# DA.net
KiCad netlist of a schematic drawn in EAGLE
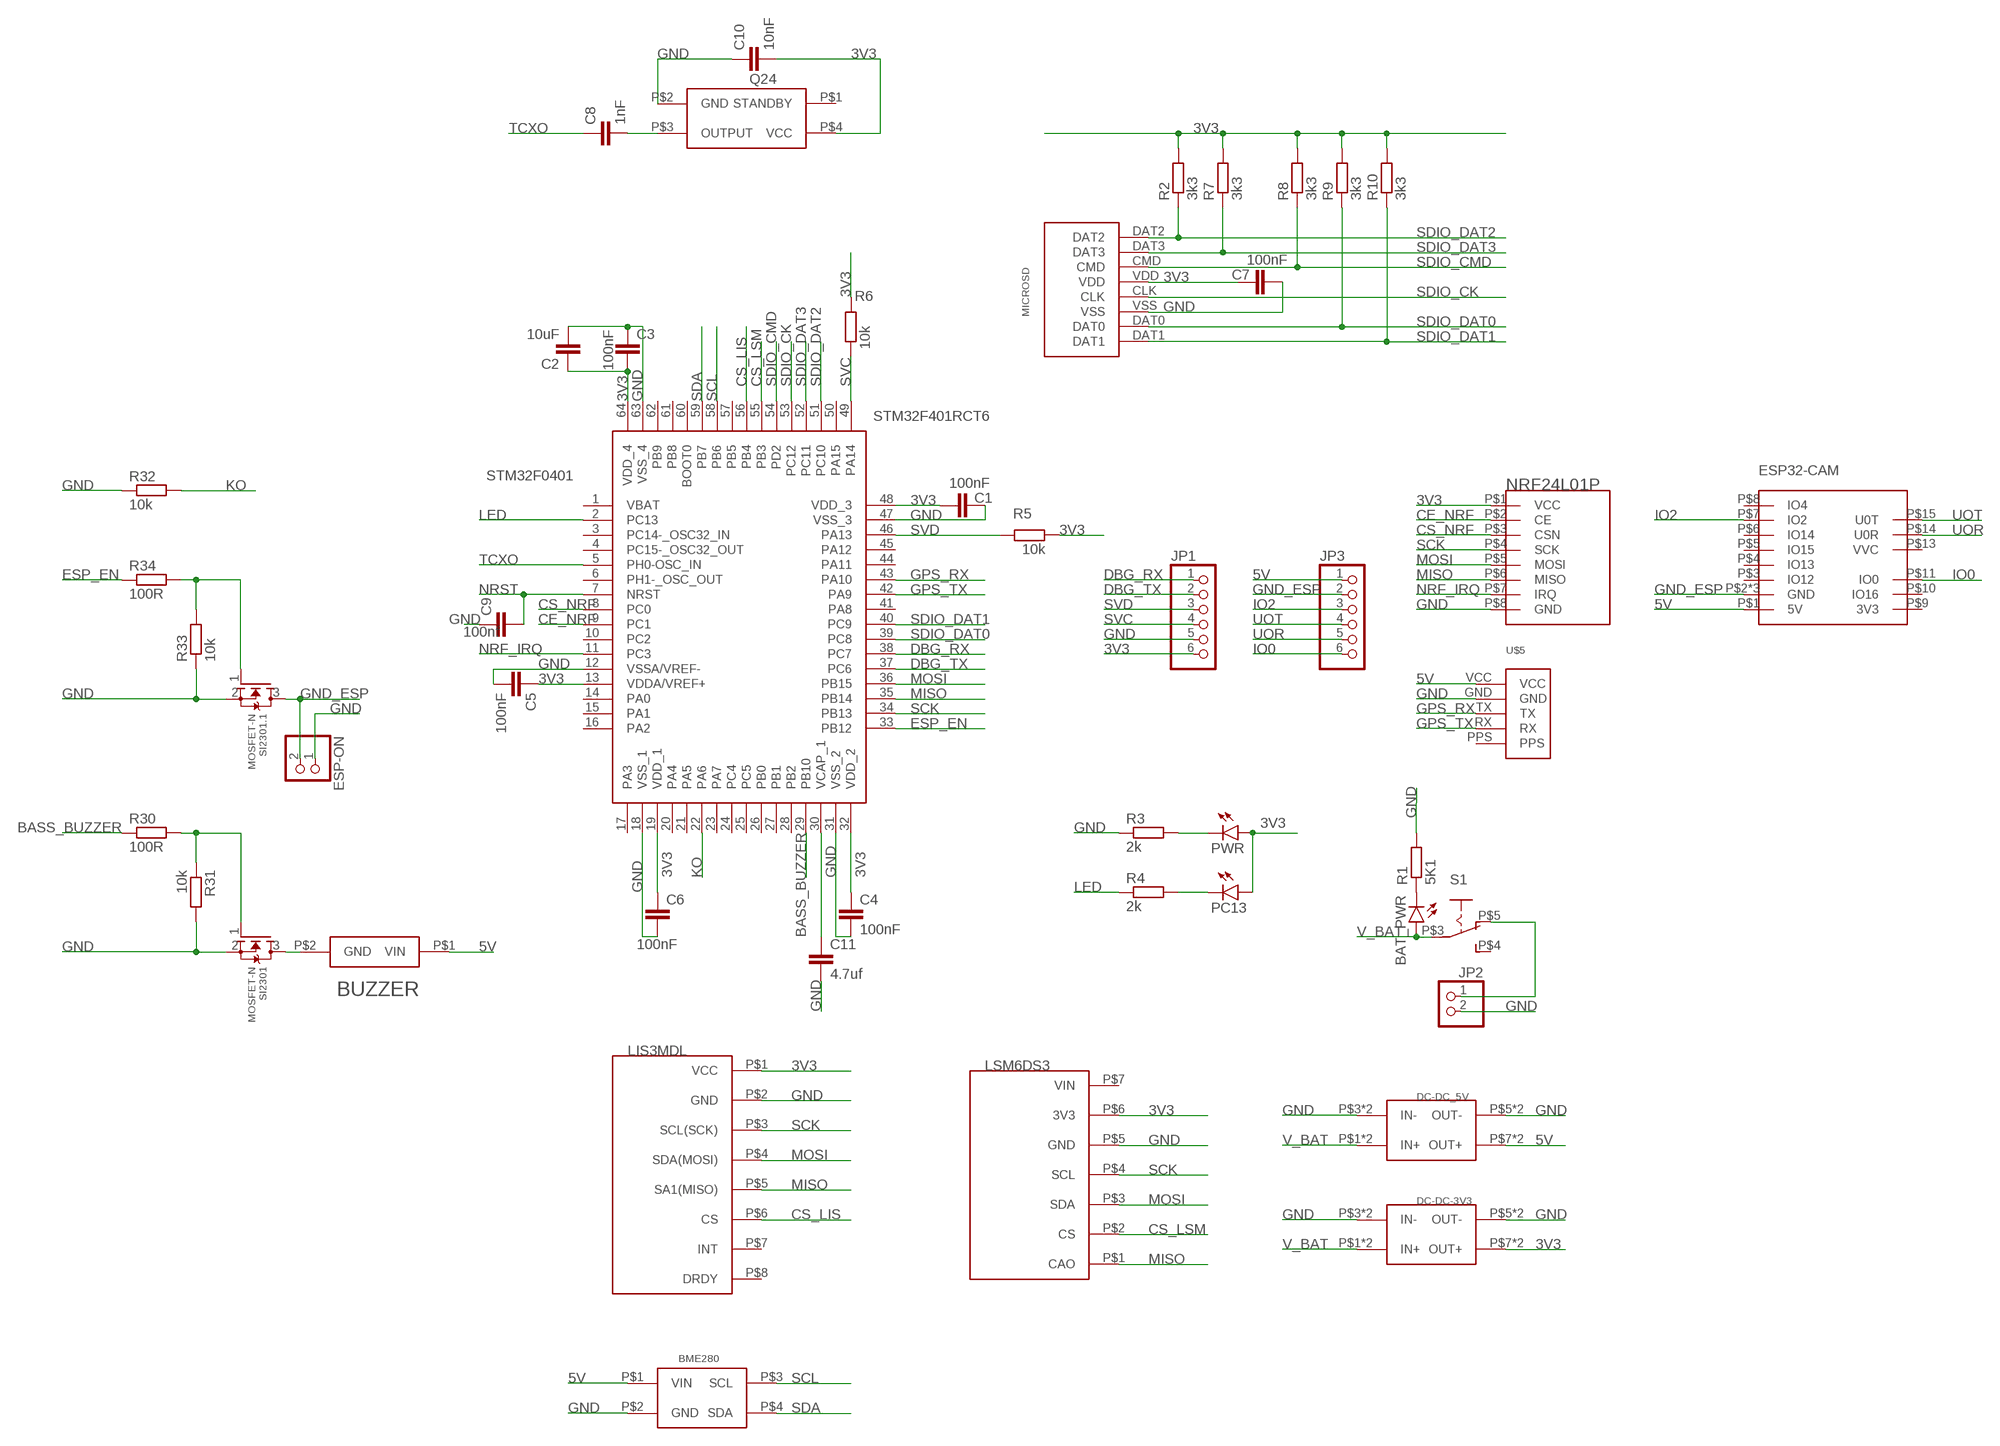
[diagram p0: schematic, sheet 1]

(export (version "E")
  (design (tool "Eeschema 10.0.6"))
  (components
    (comp (ref "BAT_PWR")
      (value "LEDSML0603")
      (footprint "eagle-import:SML0603")
      (libsource (lib "eagle-import") (part "LEDSML0603"))
    )
    (comp (ref "BME280")
      (value "BME280BME280-PINS-ONLY")
      (footprint "eagle-import:BME280-PINS-ONLY")
      (libsource (lib "eagle-import") (part "BME280BME280-PINS-ONLY"))
    )
    (comp (ref "BUZZER")
      (value "BUZZERS8R6")
      (footprint "eagle-import:BUZZER-S8R12")
      (libsource (lib "eagle-import") (part "BUZZERS8R6"))
    )
    (comp (ref "C1")
      (value "100nF")
      (footprint "eagle-import:C0603")
      (libsource (lib "eagle-import") (part "C-EUC0603"))
    )
    (comp (ref "C2")
      (value "10uF")
      (footprint "eagle-import:C1206")
      (libsource (lib "eagle-import") (part "C-EUC1206"))
    )
    (comp (ref "C3")
      (value "100nF")
      (footprint "eagle-import:C0603")
      (libsource (lib "eagle-import") (part "C-EUC0603"))
    )
    (comp (ref "C4")
      (value "100nF")
      (footprint "eagle-import:C0603")
      (libsource (lib "eagle-import") (part "C-EUC0603"))
    )
    (comp (ref "C5")
      (value "100nF")
      (footprint "eagle-import:C0603")
      (libsource (lib "eagle-import") (part "C-EUC0603"))
    )
    (comp (ref "C6")
      (value "100nF")
      (footprint "eagle-import:C0603")
      (libsource (lib "eagle-import") (part "C-EUC0603"))
    )
    (comp (ref "C7")
      (value "100nF")
      (footprint "eagle-import:C0603")
      (libsource (lib "eagle-import") (part "C-EUC0603"))
    )
    (comp (ref "C8")
      (value "1nF")
      (footprint "eagle-import:C0603")
      (libsource (lib "eagle-import") (part "C-EUC0603"))
    )
    (comp (ref "C9")
      (value "100nf")
      (footprint "eagle-import:C0603")
      (libsource (lib "eagle-import") (part "C-EUC0603"))
    )
    (comp (ref "C10")
      (value "10nF")
      (footprint "eagle-import:C0603")
      (libsource (lib "eagle-import") (part "C-EUC0603"))
    )
    (comp (ref "C11")
      (value "4.7uf")
      (footprint "eagle-import:C0603")
      (libsource (lib "eagle-import") (part "C-EUC0603"))
    )
    (comp (ref "DC-DC-3V3")
      (value "MP1584-B")
      (footprint "eagle-import:MP1584-B")
      (libsource (lib "eagle-import") (part "MP1584-B"))
    )
    (comp (ref "DC-DC_5V")
      (value "MP1584-B")
      (footprint "eagle-import:MP1584-B")
      (libsource (lib "eagle-import") (part "MP1584-B"))
    )
    (comp (ref "ESP-ON")
      (value "PINHD-1X2")
      (footprint "eagle-import:1X02")
      (libsource (lib "eagle-import") (part "PINHD-1X2"))
    )
    (comp (ref "ESP32-CAM")
      (value "ESP32-CAM")
      (footprint "eagle-import:ESP32-CAM")
      (libsource (lib "eagle-import") (part "ESP32-CAM"))
    )
    (comp (ref "JP1")
      (value "PINHD-1X6")
      (footprint "eagle-import:1X06")
      (libsource (lib "eagle-import") (part "PINHD-1X6"))
    )
    (comp (ref "JP2")
      (value "PINHD-1X2")
      (footprint "eagle-import:1X02")
      (libsource (lib "eagle-import") (part "PINHD-1X2"))
    )
    (comp (ref "JP3")
      (value "PINHD-1X6")
      (footprint "eagle-import:1X06")
      (libsource (lib "eagle-import") (part "PINHD-1X6"))
    )
    (comp (ref "LIS3MDL")
      (value "LIS3MDL-CJMCUбез_отв.")
      (footprint "eagle-import:LIS3MDL-CGMSU-NB2023-1")
      (libsource (lib "eagle-import") (part "LIS3MDL-CJMCUбез_отв."))
    )
    (comp (ref "LSM6DS3")
      (value "LSM6DS3-GY-NB2023Без_отв.")
      (footprint "eagle-import:LSM6DS3-GY-NB2023-1")
      (libsource (lib "eagle-import") (part "LSM6DS3-GY-NB2023Без_отв."))
    )
    (comp (ref "MICROSD")
      (value "SD")
      (footprint "eagle-import:SD")
      (libsource (lib "eagle-import") (part "SD"))
    )
    (comp (ref "NRF24L01P")
      (value "NRF24L01_ML01SP4")
      (footprint "eagle-import:NRF24L01_ML01SP4")
      (libsource (lib "eagle-import") (part "NRF24L01_ML01SP4"))
    )
    (comp (ref "PC13")
      (value "LEDCHIPLED_0603")
      (footprint "eagle-import:CHIPLED_0603")
      (libsource (lib "eagle-import") (part "LEDCHIPLED_0603"))
    )
    (comp (ref "PWR")
      (value "LEDCHIPLED_0603")
      (footprint "eagle-import:CHIPLED_0603")
      (libsource (lib "eagle-import") (part "LEDCHIPLED_0603"))
    )
    (comp (ref "Q24")
      (value "Q24")
      (footprint "eagle-import:Q24")
      (libsource (lib "eagle-import") (part "Q24"))
    )
    (comp (ref "R1")
      (value "5K1")
      (footprint "eagle-import:R0603")
      (libsource (lib "eagle-import") (part "R-EU_R0603"))
    )
    (comp (ref "R2")
      (value "3k3")
      (footprint "eagle-import:R0603")
      (libsource (lib "eagle-import") (part "R-EU_R0603"))
    )
    (comp (ref "R3")
      (value "2k")
      (footprint "eagle-import:R0603")
      (libsource (lib "eagle-import") (part "R-EU_R0603"))
    )
    (comp (ref "R4")
      (value "2k")
      (footprint "eagle-import:R0603")
      (libsource (lib "eagle-import") (part "R-EU_R0603"))
    )
    (comp (ref "R5")
      (value "10k")
      (footprint "eagle-import:R0603")
      (libsource (lib "eagle-import") (part "R-EU_R0603"))
    )
    (comp (ref "R6")
      (value "10k")
      (footprint "eagle-import:R0603")
      (libsource (lib "eagle-import") (part "R-EU_R0603"))
    )
    (comp (ref "R7")
      (value "3k3")
      (footprint "eagle-import:R0603")
      (libsource (lib "eagle-import") (part "R-EU_R0603"))
    )
    (comp (ref "R8")
      (value "3k3")
      (footprint "eagle-import:R0603")
      (libsource (lib "eagle-import") (part "R-EU_R0603"))
    )
    (comp (ref "R9")
      (value "3k3")
      (footprint "eagle-import:R0603")
      (libsource (lib "eagle-import") (part "R-EU_R0603"))
    )
    (comp (ref "R10")
      (value "3k3")
      (footprint "eagle-import:R0603")
      (libsource (lib "eagle-import") (part "R-EU_R0603"))
    )
    (comp (ref "R30")
      (value "100R")
      (footprint "eagle-import:R0603")
      (libsource (lib "eagle-import") (part "R-EU_R0603"))
    )
    (comp (ref "R31")
      (value "10k")
      (footprint "eagle-import:R0603")
      (libsource (lib "eagle-import") (part "R-EU_R0603"))
    )
    (comp (ref "R32")
      (value "10k")
      (footprint "eagle-import:R0603")
      (libsource (lib "eagle-import") (part "R-EU_R0603"))
    )
    (comp (ref "R33")
      (value "10k")
      (footprint "eagle-import:R0603")
      (libsource (lib "eagle-import") (part "R-EU_R0603"))
    )
    (comp (ref "R34")
      (value "100R")
      (footprint "eagle-import:R0603")
      (libsource (lib "eagle-import") (part "R-EU_R0603"))
    )
    (comp (ref "S1")
      (value "UNICS-SWITCH")
      (footprint "eagle-import:SWITCH_SK-12F14")
      (libsource (lib "eagle-import") (part "UNICS-SWITCH"))
    )
    (comp (ref "SI2301")
      (value "MOSFET-N")
      (footprint "eagle-import:SOT23-3")
      (libsource (lib "eagle-import") (part "MOSFET-N"))
    )
    (comp (ref "SI2301.1")
      (value "MOSFET-N")
      (footprint "eagle-import:SOT23-3")
      (libsource (lib "eagle-import") (part "MOSFET-N"))
    )
    (comp (ref "STM32F0401")
      (value "STM32F401RCT6")
      (footprint "eagle-import:QFP50P1200X1200X160-64N")
      (fields (field (name "MOUSER_PART_NUMBER") "511-STM32F401RCT6"))
      (libsource (lib "eagle-import") (part "STM32F401RCT6"))
    )
    (comp (ref "U$5")
      (value "GPS_NEO7M_W-PPS")
      (footprint "eagle-import:GPS_NEO7M_W-PPS_&_ANT")
      (libsource (lib "eagle-import") (part "GPS_NEO7M_W-PPS"))
    )
  )
  (nets
    (net (code "1") (name "/3V3") (class "Default")
      (node (ref "C1") (pin "2") (pinfunction "2_2") (pintype "passive"))
      (node (ref "C10") (pin "2") (pinfunction "2_2") (pintype "passive"))
      (node (ref "C2") (pin "1") (pinfunction "1_1") (pintype "passive"))
      (node (ref "C3") (pin "2") (pinfunction "2_2") (pintype "passive"))
      (node (ref "C4") (pin "1") (pinfunction "1_1") (pintype "passive"))
      (node (ref "C5") (pin "1") (pinfunction "1_1") (pintype "passive"))
      (node (ref "C6") (pin "1") (pinfunction "1_1") (pintype "passive"))
      (node (ref "C7") (pin "2") (pinfunction "2_2") (pintype "passive"))
      (node (ref "DC-DC-3V3") (pin "P$7") (pinfunction "OUT+_P$7") (pintype "bidirectional"))
      (node (ref "DC-DC-3V3") (pin "P$8") (pinfunction "OUT+_P$8") (pintype "bidirectional"))
      (node (ref "JP1") (pin "6") (pinfunction "6_6") (pintype "passive"))
      (node (ref "LIS3MDL") (pin "P$1") (pinfunction "VCC_P$1") (pintype "bidirectional"))
      (node (ref "LSM6DS3") (pin "P$6") (pinfunction "3V3_P$6") (pintype "bidirectional"))
      (node (ref "MICROSD") (pin "VDD") (pinfunction "VDD_VDD") (pintype "bidirectional"))
      (node (ref "NRF24L01P") (pin "P$1") (pinfunction "VCC_P$1") (pintype "bidirectional"))
      (node (ref "PC13") (pin "A") (pinfunction "A_A") (pintype "passive"))
      (node (ref "PWR") (pin "A") (pinfunction "A_A") (pintype "passive"))
      (node (ref "Q24") (pin "P$4") (pinfunction "VCC_P$4") (pintype "bidirectional"))
      (node (ref "R10") (pin "2") (pinfunction "2_2") (pintype "passive"))
      (node (ref "R2") (pin "2") (pinfunction "2_2") (pintype "passive"))
      (node (ref "R5") (pin "2") (pinfunction "2_2") (pintype "passive"))
      (node (ref "R6") (pin "2") (pinfunction "2_2") (pintype "passive"))
      (node (ref "R7") (pin "2") (pinfunction "2_2") (pintype "passive"))
      (node (ref "R8") (pin "2") (pinfunction "2_2") (pintype "passive"))
      (node (ref "R9") (pin "2") (pinfunction "2_2") (pintype "passive"))
      (node (ref "STM32F0401") (pin "13") (pinfunction "VDDA/VREF+_13") (pintype "bidirectional"))
      (node (ref "STM32F0401") (pin "19") (pinfunction "VDD_1_19") (pintype "bidirectional"))
      (node (ref "STM32F0401") (pin "32") (pinfunction "VDD_2_32") (pintype "bidirectional"))
      (node (ref "STM32F0401") (pin "48") (pinfunction "VDD_3_48") (pintype "bidirectional"))
      (node (ref "STM32F0401") (pin "64") (pinfunction "VDD_4_64") (pintype "bidirectional"))
    )
    (net (code "2") (name "/5V") (class "Default")
      (node (ref "BME280") (pin "P$1") (pinfunction "VIN_P$1") (pintype "bidirectional"))
      (node (ref "BUZZER") (pin "P$1") (pinfunction "VIN_P$1") (pintype "bidirectional"))
      (node (ref "DC-DC_5V") (pin "P$7") (pinfunction "OUT+_P$7") (pintype "bidirectional"))
      (node (ref "DC-DC_5V") (pin "P$8") (pinfunction "OUT+_P$8") (pintype "bidirectional"))
      (node (ref "ESP32-CAM") (pin "P$1") (pinfunction "5V_P$1") (pintype "bidirectional"))
      (node (ref "JP3") (pin "1") (pinfunction "1_1") (pintype "passive"))
      (node (ref "U$5") (pin "VCC") (pinfunction "VCC_VCC") (pintype "bidirectional"))
    )
    (net (code "3") (name "/BASS_BUZZER") (class "Default")
      (node (ref "R30") (pin "1") (pinfunction "1_1") (pintype "passive"))
      (node (ref "STM32F0401") (pin "29") (pinfunction "PB10_29") (pintype "bidirectional"))
    )
    (net (code "4") (name "/CE_NRF") (class "Default")
      (node (ref "NRF24L01P") (pin "P$2") (pinfunction "CE_P$2") (pintype "bidirectional"))
      (node (ref "STM32F0401") (pin "9") (pinfunction "PC1_9") (pintype "bidirectional"))
    )
    (net (code "5") (name "/CS_LIS") (class "Default")
      (node (ref "LIS3MDL") (pin "P$6") (pinfunction "CS_P$6") (pintype "bidirectional"))
      (node (ref "STM32F0401") (pin "56") (pinfunction "PB4_56") (pintype "bidirectional"))
    )
    (net (code "6") (name "/CS_LSM") (class "Default")
      (node (ref "LSM6DS3") (pin "P$2") (pinfunction "CS_P$2") (pintype "bidirectional"))
      (node (ref "STM32F0401") (pin "55") (pinfunction "PB3_55") (pintype "bidirectional"))
    )
    (net (code "7") (name "/CS_NRF") (class "Default")
      (node (ref "NRF24L01P") (pin "P$3") (pinfunction "CSN_P$3") (pintype "bidirectional"))
      (node (ref "STM32F0401") (pin "8") (pinfunction "PC0_8") (pintype "bidirectional"))
    )
    (net (code "8") (name "/DBG_RX") (class "Default")
      (node (ref "JP1") (pin "1") (pinfunction "1_1") (pintype "passive"))
      (node (ref "STM32F0401") (pin "38") (pinfunction "PC7_38") (pintype "bidirectional"))
    )
    (net (code "9") (name "/DBG_TX") (class "Default")
      (node (ref "JP1") (pin "2") (pinfunction "2_2") (pintype "passive"))
      (node (ref "STM32F0401") (pin "37") (pinfunction "PC6_37") (pintype "bidirectional"))
    )
    (net (code "10") (name "/ESP_EN") (class "Default")
      (node (ref "R34") (pin "1") (pinfunction "1_1") (pintype "passive"))
      (node (ref "STM32F0401") (pin "33") (pinfunction "PB12_33") (pintype "bidirectional"))
    )
    (net (code "11") (name "/GND") (class "Default")
      (node (ref "BME280") (pin "P$2") (pinfunction "GND_P$2") (pintype "bidirectional"))
      (node (ref "C1") (pin "1") (pinfunction "1_1") (pintype "passive"))
      (node (ref "C10") (pin "1") (pinfunction "1_1") (pintype "passive"))
      (node (ref "C11") (pin "2") (pinfunction "2_2") (pintype "passive"))
      (node (ref "C2") (pin "2") (pinfunction "2_2") (pintype "passive"))
      (node (ref "C3") (pin "1") (pinfunction "1_1") (pintype "passive"))
      (node (ref "C4") (pin "2") (pinfunction "2_2") (pintype "passive"))
      (node (ref "C5") (pin "2") (pinfunction "2_2") (pintype "passive"))
      (node (ref "C6") (pin "2") (pinfunction "2_2") (pintype "passive"))
      (node (ref "C7") (pin "1") (pinfunction "1_1") (pintype "passive"))
      (node (ref "C9") (pin "1") (pinfunction "1_1") (pintype "passive"))
      (node (ref "DC-DC-3V3") (pin "P$3") (pinfunction "IN-_P$3") (pintype "bidirectional"))
      (node (ref "DC-DC-3V3") (pin "P$4") (pinfunction "IN-_P$4") (pintype "bidirectional"))
      (node (ref "DC-DC-3V3") (pin "P$5") (pinfunction "OUT-_P$5") (pintype "bidirectional"))
      (node (ref "DC-DC-3V3") (pin "P$6") (pinfunction "OUT-_P$6") (pintype "bidirectional"))
      (node (ref "DC-DC_5V") (pin "P$3") (pinfunction "IN-_P$3") (pintype "bidirectional"))
      (node (ref "DC-DC_5V") (pin "P$4") (pinfunction "IN-_P$4") (pintype "bidirectional"))
      (node (ref "DC-DC_5V") (pin "P$5") (pinfunction "OUT-_P$5") (pintype "bidirectional"))
      (node (ref "DC-DC_5V") (pin "P$6") (pinfunction "OUT-_P$6") (pintype "bidirectional"))
      (node (ref "ESP-ON") (pin "1") (pinfunction "1_1") (pintype "passive"))
      (node (ref "JP1") (pin "5") (pinfunction "5_5") (pintype "passive"))
      (node (ref "JP2") (pin "2") (pinfunction "2_2") (pintype "passive"))
      (node (ref "LIS3MDL") (pin "P$2") (pinfunction "GND_P$2") (pintype "bidirectional"))
      (node (ref "LSM6DS3") (pin "P$5") (pinfunction "GND_P$5") (pintype "bidirectional"))
      (node (ref "MICROSD") (pin "VSS") (pinfunction "VSS_VSS") (pintype "bidirectional"))
      (node (ref "NRF24L01P") (pin "P$8") (pinfunction "GND_P$8") (pintype "bidirectional"))
      (node (ref "Q24") (pin "P$2") (pinfunction "GND_P$2") (pintype "bidirectional"))
      (node (ref "R1") (pin "2") (pinfunction "2_2") (pintype "passive"))
      (node (ref "R3") (pin "1") (pinfunction "1_1") (pintype "passive"))
      (node (ref "R31") (pin "2") (pinfunction "2_2") (pintype "passive"))
      (node (ref "R32") (pin "1") (pinfunction "1_1") (pintype "passive"))
      (node (ref "R33") (pin "1") (pinfunction "1_1") (pintype "passive"))
      (node (ref "SI2301") (pin "2") (pinfunction "S_2") (pintype "bidirectional"))
      (node (ref "SI2301.1") (pin "2") (pinfunction "S_2") (pintype "bidirectional"))
      (node (ref "STM32F0401") (pin "12") (pinfunction "VSSA/VREF-_12") (pintype "bidirectional"))
      (node (ref "STM32F0401") (pin "18") (pinfunction "VSS_1_18") (pintype "bidirectional"))
      (node (ref "STM32F0401") (pin "31") (pinfunction "VSS_2_31") (pintype "bidirectional"))
      (node (ref "STM32F0401") (pin "47") (pinfunction "VSS_3_47") (pintype "bidirectional"))
      (node (ref "STM32F0401") (pin "63") (pinfunction "VSS_4_63") (pintype "bidirectional"))
      (node (ref "U$5") (pin "GND") (pinfunction "GND_GND") (pintype "bidirectional"))
    )
    (net (code "12") (name "/GND_ESP") (class "Default")
      (node (ref "ESP-ON") (pin "2") (pinfunction "2_2") (pintype "passive"))
      (node (ref "ESP32-CAM") (pin "P$12") (pinfunction "GND_P$12") (pintype "bidirectional"))
      (node (ref "ESP32-CAM") (pin "P$16") (pinfunction "GND_P$16") (pintype "bidirectional"))
      (node (ref "ESP32-CAM") (pin "P$2") (pinfunction "GND_P$2") (pintype "bidirectional"))
      (node (ref "JP3") (pin "2") (pinfunction "2_2") (pintype "passive"))
      (node (ref "SI2301.1") (pin "3") (pinfunction "D_3") (pintype "bidirectional"))
    )
    (net (code "13") (name "/GPS_RX") (class "Default")
      (node (ref "STM32F0401") (pin "43") (pinfunction "PA10_43") (pintype "bidirectional"))
      (node (ref "U$5") (pin "TX") (pinfunction "TX_TX") (pintype "bidirectional"))
    )
    (net (code "14") (name "/GPS_TX") (class "Default")
      (node (ref "STM32F0401") (pin "42") (pinfunction "PA9_42") (pintype "bidirectional"))
      (node (ref "U$5") (pin "RX") (pinfunction "RX_RX") (pintype "bidirectional"))
    )
    (net (code "15") (name "/IO0") (class "Default")
      (node (ref "ESP32-CAM") (pin "P$11") (pinfunction "IO0_P$11") (pintype "bidirectional"))
      (node (ref "JP3") (pin "6") (pinfunction "6_6") (pintype "passive"))
    )
    (net (code "16") (name "/IO2") (class "Default")
      (node (ref "ESP32-CAM") (pin "P$7") (pinfunction "IO2_P$7") (pintype "bidirectional"))
      (node (ref "JP3") (pin "3") (pinfunction "3_3") (pintype "passive"))
    )
    (net (code "17") (name "/KO") (class "Default")
      (node (ref "R32") (pin "2") (pinfunction "2_2") (pintype "passive"))
      (node (ref "STM32F0401") (pin "22") (pinfunction "PA6_22") (pintype "bidirectional"))
    )
    (net (code "18") (name "/LED") (class "Default")
      (node (ref "R4") (pin "1") (pinfunction "1_1") (pintype "passive"))
      (node (ref "STM32F0401") (pin "2") (pinfunction "PC13_2") (pintype "bidirectional"))
    )
    (net (code "19") (name "/MISO") (class "Default")
      (node (ref "LIS3MDL") (pin "P$5") (pinfunction "SA1(MISO)_P$5") (pintype "bidirectional"))
      (node (ref "LSM6DS3") (pin "P$1") (pinfunction "CAO_P$1") (pintype "bidirectional"))
      (node (ref "NRF24L01P") (pin "P$6") (pinfunction "MISO_P$6") (pintype "bidirectional"))
      (node (ref "STM32F0401") (pin "35") (pinfunction "PB14_35") (pintype "bidirectional"))
    )
    (net (code "20") (name "/MOSI") (class "Default")
      (node (ref "LIS3MDL") (pin "P$4") (pinfunction "SDA(MOSI)_P$4") (pintype "bidirectional"))
      (node (ref "LSM6DS3") (pin "P$3") (pinfunction "SDA_P$3") (pintype "bidirectional"))
      (node (ref "NRF24L01P") (pin "P$5") (pinfunction "MOSI_P$5") (pintype "bidirectional"))
      (node (ref "STM32F0401") (pin "36") (pinfunction "PB15_36") (pintype "bidirectional"))
    )
    (net (code "21") (name "/NRF_IRQ") (class "Default")
      (node (ref "NRF24L01P") (pin "P$7") (pinfunction "IRQ_P$7") (pintype "bidirectional"))
      (node (ref "STM32F0401") (pin "11") (pinfunction "PC3_11") (pintype "bidirectional"))
    )
    (net (code "22") (name "/NRST") (class "Default")
      (node (ref "C9") (pin "2") (pinfunction "2_2") (pintype "passive"))
      (node (ref "STM32F0401") (pin "7") (pinfunction "NRST_7") (pintype "bidirectional"))
    )
    (net (code "23") (name "/SCK") (class "Default")
      (node (ref "LIS3MDL") (pin "P$3") (pinfunction "SCL(SCK)_P$3") (pintype "bidirectional"))
      (node (ref "LSM6DS3") (pin "P$4") (pinfunction "SCL_P$4") (pintype "bidirectional"))
      (node (ref "NRF24L01P") (pin "P$4") (pinfunction "SCK_P$4") (pintype "bidirectional"))
      (node (ref "STM32F0401") (pin "34") (pinfunction "PB13_34") (pintype "bidirectional"))
    )
    (net (code "24") (name "/SCL") (class "Default")
      (node (ref "BME280") (pin "P$3") (pinfunction "SCL_P$3") (pintype "bidirectional"))
      (node (ref "STM32F0401") (pin "58") (pinfunction "PB6_58") (pintype "bidirectional"))
    )
    (net (code "25") (name "/SDA") (class "Default")
      (node (ref "BME280") (pin "P$4") (pinfunction "SDA_P$4") (pintype "bidirectional"))
      (node (ref "STM32F0401") (pin "59") (pinfunction "PB7_59") (pintype "bidirectional"))
    )
    (net (code "26") (name "/SDIO_CK") (class "Default")
      (node (ref "MICROSD") (pin "CLK") (pinfunction "CLK_CLK") (pintype "bidirectional"))
      (node (ref "STM32F0401") (pin "53") (pinfunction "PC12_53") (pintype "bidirectional"))
    )
    (net (code "27") (name "/SDIO_CMD") (class "Default")
      (node (ref "MICROSD") (pin "CMD") (pinfunction "CMD_CMD") (pintype "bidirectional"))
      (node (ref "R8") (pin "1") (pinfunction "1_1") (pintype "passive"))
      (node (ref "STM32F0401") (pin "54") (pinfunction "PD2_54") (pintype "bidirectional"))
    )
    (net (code "28") (name "/SDIO_DAT0") (class "Default")
      (node (ref "MICROSD") (pin "DAT0") (pinfunction "DAT0_DAT0") (pintype "bidirectional"))
      (node (ref "R9") (pin "1") (pinfunction "1_1") (pintype "passive"))
      (node (ref "STM32F0401") (pin "39") (pinfunction "PC8_39") (pintype "bidirectional"))
    )
    (net (code "29") (name "/SDIO_DAT1") (class "Default")
      (node (ref "MICROSD") (pin "DAT1") (pinfunction "DAT1_DAT1") (pintype "bidirectional"))
      (node (ref "R10") (pin "1") (pinfunction "1_1") (pintype "passive"))
      (node (ref "STM32F0401") (pin "40") (pinfunction "PC9_40") (pintype "bidirectional"))
    )
    (net (code "30") (name "/SDIO_DAT2") (class "Default")
      (node (ref "MICROSD") (pin "DAT2") (pinfunction "DAT2_DAT2") (pintype "bidirectional"))
      (node (ref "R2") (pin "1") (pinfunction "1_1") (pintype "passive"))
      (node (ref "STM32F0401") (pin "51") (pinfunction "PC10_51") (pintype "bidirectional"))
    )
    (net (code "31") (name "/SDIO_DAT3") (class "Default")
      (node (ref "MICROSD") (pin "DAT3") (pinfunction "DAT3_DAT3") (pintype "bidirectional"))
      (node (ref "R7") (pin "1") (pinfunction "1_1") (pintype "passive"))
      (node (ref "STM32F0401") (pin "52") (pinfunction "PC11_52") (pintype "bidirectional"))
    )
    (net (code "32") (name "/SVC") (class "Default")
      (node (ref "JP1") (pin "4") (pinfunction "4_4") (pintype "passive"))
      (node (ref "R6") (pin "1") (pinfunction "1_1") (pintype "passive"))
      (node (ref "STM32F0401") (pin "49") (pinfunction "PA14_49") (pintype "bidirectional"))
    )
    (net (code "33") (name "/SVD") (class "Default")
      (node (ref "JP1") (pin "3") (pinfunction "3_3") (pintype "passive"))
      (node (ref "R5") (pin "1") (pinfunction "1_1") (pintype "passive"))
      (node (ref "STM32F0401") (pin "46") (pinfunction "PA13_46") (pintype "bidirectional"))
    )
    (net (code "34") (name "/TCXO") (class "Default")
      (node (ref "C8") (pin "1") (pinfunction "1_1") (pintype "passive"))
      (node (ref "STM32F0401") (pin "5") (pinfunction "PH0-OSC_IN_5") (pintype "bidirectional"))
    )
    (net (code "35") (name "/UOR") (class "Default")
      (node (ref "ESP32-CAM") (pin "P$14") (pinfunction "U0R_P$14") (pintype "bidirectional"))
      (node (ref "JP3") (pin "5") (pinfunction "5_5") (pintype "passive"))
    )
    (net (code "36") (name "/UOT") (class "Default")
      (node (ref "ESP32-CAM") (pin "P$15") (pinfunction "U0T_P$15") (pintype "bidirectional"))
      (node (ref "JP3") (pin "4") (pinfunction "4_4") (pintype "passive"))
    )
    (net (code "37") (name "/V_BAT") (class "Default")
      (node (ref "BAT_PWR") (pin "A") (pinfunction "A_A") (pintype "passive"))
      (node (ref "DC-DC-3V3") (pin "P$1") (pinfunction "IN+_P$1") (pintype "bidirectional"))
      (node (ref "DC-DC-3V3") (pin "P$2") (pinfunction "IN+_P$2") (pintype "bidirectional"))
      (node (ref "DC-DC_5V") (pin "P$1") (pinfunction "IN+_P$1") (pintype "bidirectional"))
      (node (ref "DC-DC_5V") (pin "P$2") (pinfunction "IN+_P$2") (pintype "bidirectional"))
      (node (ref "S1") (pin "P$3") (pinfunction "P_P$3") (pintype "passive"))
    )
    (net (code "38") (name "Net-(BAT_PWR-PadC)") (class "Default")
      (node (ref "BAT_PWR") (pin "C") (pinfunction "C_C") (pintype "passive"))
      (node (ref "R1") (pin "1") (pinfunction "1_1") (pintype "passive"))
    )
    (net (code "39") (name "Net-(BUZZER-GND)") (class "Default")
      (node (ref "BUZZER") (pin "P$2") (pinfunction "GND_P$2") (pintype "bidirectional"))
      (node (ref "SI2301") (pin "3") (pinfunction "D_3") (pintype "bidirectional"))
    )
    (net (code "40") (name "Net-(PC13-PadC)") (class "Default")
      (node (ref "PC13") (pin "C") (pinfunction "C_C") (pintype "passive"))
      (node (ref "R4") (pin "2") (pinfunction "2_2") (pintype "passive"))
    )
    (net (code "41") (name "Net-(PWR-PadC)") (class "Default")
      (node (ref "PWR") (pin "C") (pinfunction "C_C") (pintype "passive"))
      (node (ref "R3") (pin "2") (pinfunction "2_2") (pintype "passive"))
    )
    (net (code "42") (name "Net-(Q24-OUTPUT)") (class "Default")
      (node (ref "C8") (pin "2") (pinfunction "2_2") (pintype "passive"))
      (node (ref "Q24") (pin "P$3") (pinfunction "OUTPUT_P$3") (pintype "bidirectional"))
    )
    (net (code "43") (name "Net-(S1-O)") (class "Default")
      (node (ref "JP2") (pin "1") (pinfunction "1_1") (pintype "passive"))
      (node (ref "S1") (pin "P$5") (pinfunction "O_P$5") (pintype "passive"))
    )
    (net (code "44") (name "Net-(SI2301-G)") (class "Default")
      (node (ref "R30") (pin "2") (pinfunction "2_2") (pintype "passive"))
      (node (ref "R31") (pin "1") (pinfunction "1_1") (pintype "passive"))
      (node (ref "SI2301") (pin "1") (pinfunction "G_1") (pintype "bidirectional"))
    )
    (net (code "45") (name "Net-(SI2301.1-G)") (class "Default")
      (node (ref "R33") (pin "2") (pinfunction "2_2") (pintype "passive"))
      (node (ref "R34") (pin "2") (pinfunction "2_2") (pintype "passive"))
      (node (ref "SI2301.1") (pin "1") (pinfunction "G_1") (pintype "bidirectional"))
    )
    (net (code "46") (name "Net-(STM32F0401-VCAP_1)") (class "Default")
      (node (ref "C11") (pin "1") (pinfunction "1_1") (pintype "passive"))
      (node (ref "STM32F0401") (pin "30") (pinfunction "VCAP_1_30") (pintype "bidirectional"))
    )
    (net (code "47") (name "unconnected-(ESP32-CAM-3V3-PadP$9)") (class "Default")
      (node (ref "ESP32-CAM") (pin "P$9") (pinfunction "3V3_P$9") (pintype "bidirectional"))
    )
    (net (code "48") (name "unconnected-(ESP32-CAM-IO4-PadP$8)") (class "Default")
      (node (ref "ESP32-CAM") (pin "P$8") (pinfunction "IO4_P$8") (pintype "bidirectional"))
    )
    (net (code "49") (name "unconnected-(ESP32-CAM-IO12-PadP$3)") (class "Default")
      (node (ref "ESP32-CAM") (pin "P$3") (pinfunction "IO12_P$3") (pintype "bidirectional"))
    )
    (net (code "50") (name "unconnected-(ESP32-CAM-IO13-PadP$4)") (class "Default")
      (node (ref "ESP32-CAM") (pin "P$4") (pinfunction "IO13_P$4") (pintype "bidirectional"))
    )
    (net (code "51") (name "unconnected-(ESP32-CAM-IO14-PadP$6)") (class "Default")
      (node (ref "ESP32-CAM") (pin "P$6") (pinfunction "IO14_P$6") (pintype "bidirectional"))
    )
    (net (code "52") (name "unconnected-(ESP32-CAM-IO15-PadP$5)") (class "Default")
      (node (ref "ESP32-CAM") (pin "P$5") (pinfunction "IO15_P$5") (pintype "bidirectional"))
    )
    (net (code "53") (name "unconnected-(ESP32-CAM-IO16-PadP$10)") (class "Default")
      (node (ref "ESP32-CAM") (pin "P$10") (pinfunction "IO16_P$10") (pintype "bidirectional"))
    )
    (net (code "54") (name "unconnected-(ESP32-CAM-VVC-PadP$13)") (class "Default")
      (node (ref "ESP32-CAM") (pin "P$13") (pinfunction "VVC_P$13") (pintype "bidirectional"))
    )
    (net (code "55") (name "unconnected-(LIS3MDL-DRDY-PadP$8)") (class "Default")
      (node (ref "LIS3MDL") (pin "P$8") (pinfunction "DRDY_P$8") (pintype "bidirectional"))
    )
    (net (code "56") (name "unconnected-(LIS3MDL-INT-PadP$7)") (class "Default")
      (node (ref "LIS3MDL") (pin "P$7") (pinfunction "INT_P$7") (pintype "bidirectional"))
    )
    (net (code "57") (name "unconnected-(LSM6DS3-VIN-PadP$7)") (class "Default")
      (node (ref "LSM6DS3") (pin "P$7") (pinfunction "VIN_P$7") (pintype "bidirectional"))
    )
    (net (code "58") (name "unconnected-(Q24-STANDBY-PadP$1)") (class "Default")
      (node (ref "Q24") (pin "P$1") (pinfunction "STANDBY_P$1") (pintype "bidirectional"))
    )
    (net (code "59") (name "unconnected-(S1-S-PadP$4)") (class "Default")
      (node (ref "S1") (pin "P$4") (pinfunction "S_P$4") (pintype "passive"))
    )
    (net (code "60") (name "unconnected-(STM32F0401-BOOT0-Pad60)") (class "Default")
      (node (ref "STM32F0401") (pin "60") (pinfunction "BOOT0_60") (pintype "bidirectional"))
    )
    (net (code "61") (name "unconnected-(STM32F0401-PA0-Pad14)") (class "Default")
      (node (ref "STM32F0401") (pin "14") (pinfunction "PA0_14") (pintype "bidirectional"))
    )
    (net (code "62") (name "unconnected-(STM32F0401-PA1-Pad15)") (class "Default")
      (node (ref "STM32F0401") (pin "15") (pinfunction "PA1_15") (pintype "bidirectional"))
    )
    (net (code "63") (name "unconnected-(STM32F0401-PA2-Pad16)") (class "Default")
      (node (ref "STM32F0401") (pin "16") (pinfunction "PA2_16") (pintype "bidirectional"))
    )
    (net (code "64") (name "unconnected-(STM32F0401-PA3-Pad17)") (class "Default")
      (node (ref "STM32F0401") (pin "17") (pinfunction "PA3_17") (pintype "bidirectional"))
    )
    (net (code "65") (name "unconnected-(STM32F0401-PA4-Pad20)") (class "Default")
      (node (ref "STM32F0401") (pin "20") (pinfunction "PA4_20") (pintype "bidirectional"))
    )
    (net (code "66") (name "unconnected-(STM32F0401-PA5-Pad21)") (class "Default")
      (node (ref "STM32F0401") (pin "21") (pinfunction "PA5_21") (pintype "bidirectional"))
    )
    (net (code "67") (name "unconnected-(STM32F0401-PA7-Pad23)") (class "Default")
      (node (ref "STM32F0401") (pin "23") (pinfunction "PA7_23") (pintype "bidirectional"))
    )
    (net (code "68") (name "unconnected-(STM32F0401-PA8-Pad41)") (class "Default")
      (node (ref "STM32F0401") (pin "41") (pinfunction "PA8_41") (pintype "bidirectional"))
    )
    (net (code "69") (name "unconnected-(STM32F0401-PA11-Pad44)") (class "Default")
      (node (ref "STM32F0401") (pin "44") (pinfunction "PA11_44") (pintype "bidirectional"))
    )
    (net (code "70") (name "unconnected-(STM32F0401-PA12-Pad45)") (class "Default")
      (node (ref "STM32F0401") (pin "45") (pinfunction "PA12_45") (pintype "bidirectional"))
    )
    (net (code "71") (name "unconnected-(STM32F0401-PA15-Pad50)") (class "Default")
      (node (ref "STM32F0401") (pin "50") (pinfunction "PA15_50") (pintype "bidirectional"))
    )
    (net (code "72") (name "unconnected-(STM32F0401-PB0-Pad26)") (class "Default")
      (node (ref "STM32F0401") (pin "26") (pinfunction "PB0_26") (pintype "bidirectional"))
    )
    (net (code "73") (name "unconnected-(STM32F0401-PB1-Pad27)") (class "Default")
      (node (ref "STM32F0401") (pin "27") (pinfunction "PB1_27") (pintype "bidirectional"))
    )
    (net (code "74") (name "unconnected-(STM32F0401-PB2-Pad28)") (class "Default")
      (node (ref "STM32F0401") (pin "28") (pinfunction "PB2_28") (pintype "bidirectional"))
    )
    (net (code "75") (name "unconnected-(STM32F0401-PB5-Pad57)") (class "Default")
      (node (ref "STM32F0401") (pin "57") (pinfunction "PB5_57") (pintype "bidirectional"))
    )
    (net (code "76") (name "unconnected-(STM32F0401-PB8-Pad61)") (class "Default")
      (node (ref "STM32F0401") (pin "61") (pinfunction "PB8_61") (pintype "bidirectional"))
    )
    (net (code "77") (name "unconnected-(STM32F0401-PB9-Pad62)") (class "Default")
      (node (ref "STM32F0401") (pin "62") (pinfunction "PB9_62") (pintype "bidirectional"))
    )
    (net (code "78") (name "unconnected-(STM32F0401-PC2-Pad10)") (class "Default")
      (node (ref "STM32F0401") (pin "10") (pinfunction "PC2_10") (pintype "bidirectional"))
    )
    (net (code "79") (name "unconnected-(STM32F0401-PC4-Pad24)") (class "Default")
      (node (ref "STM32F0401") (pin "24") (pinfunction "PC4_24") (pintype "bidirectional"))
    )
    (net (code "80") (name "unconnected-(STM32F0401-PC5-Pad25)") (class "Default")
      (node (ref "STM32F0401") (pin "25") (pinfunction "PC5_25") (pintype "bidirectional"))
    )
    (net (code "81") (name "unconnected-(STM32F0401-PC14-_OSC32_IN-Pad3)") (class "Default")
      (node (ref "STM32F0401") (pin "3") (pinfunction "PC14-_OSC32_IN_3") (pintype "bidirectional"))
    )
    (net (code "82") (name "unconnected-(STM32F0401-PC15-_OSC32_OUT-Pad4)") (class "Default")
      (node (ref "STM32F0401") (pin "4") (pinfunction "PC15-_OSC32_OUT_4") (pintype "bidirectional"))
    )
    (net (code "83") (name "unconnected-(STM32F0401-PH1-_OSC_OUT-Pad6)") (class "Default")
      (node (ref "STM32F0401") (pin "6") (pinfunction "PH1-_OSC_OUT_6") (pintype "bidirectional"))
    )
    (net (code "84") (name "unconnected-(STM32F0401-VBAT-Pad1)") (class "Default")
      (node (ref "STM32F0401") (pin "1") (pinfunction "VBAT_1") (pintype "bidirectional"))
    )
    (net (code "85") (name "unconnected-(U$5-PadPPS)") (class "Default")
      (node (ref "U$5") (pin "PPS") (pinfunction "PPS_PPS") (pintype "bidirectional"))
    )
  )
)
